# main.net
KiCad netlist of a schematic drawn in EAGLE
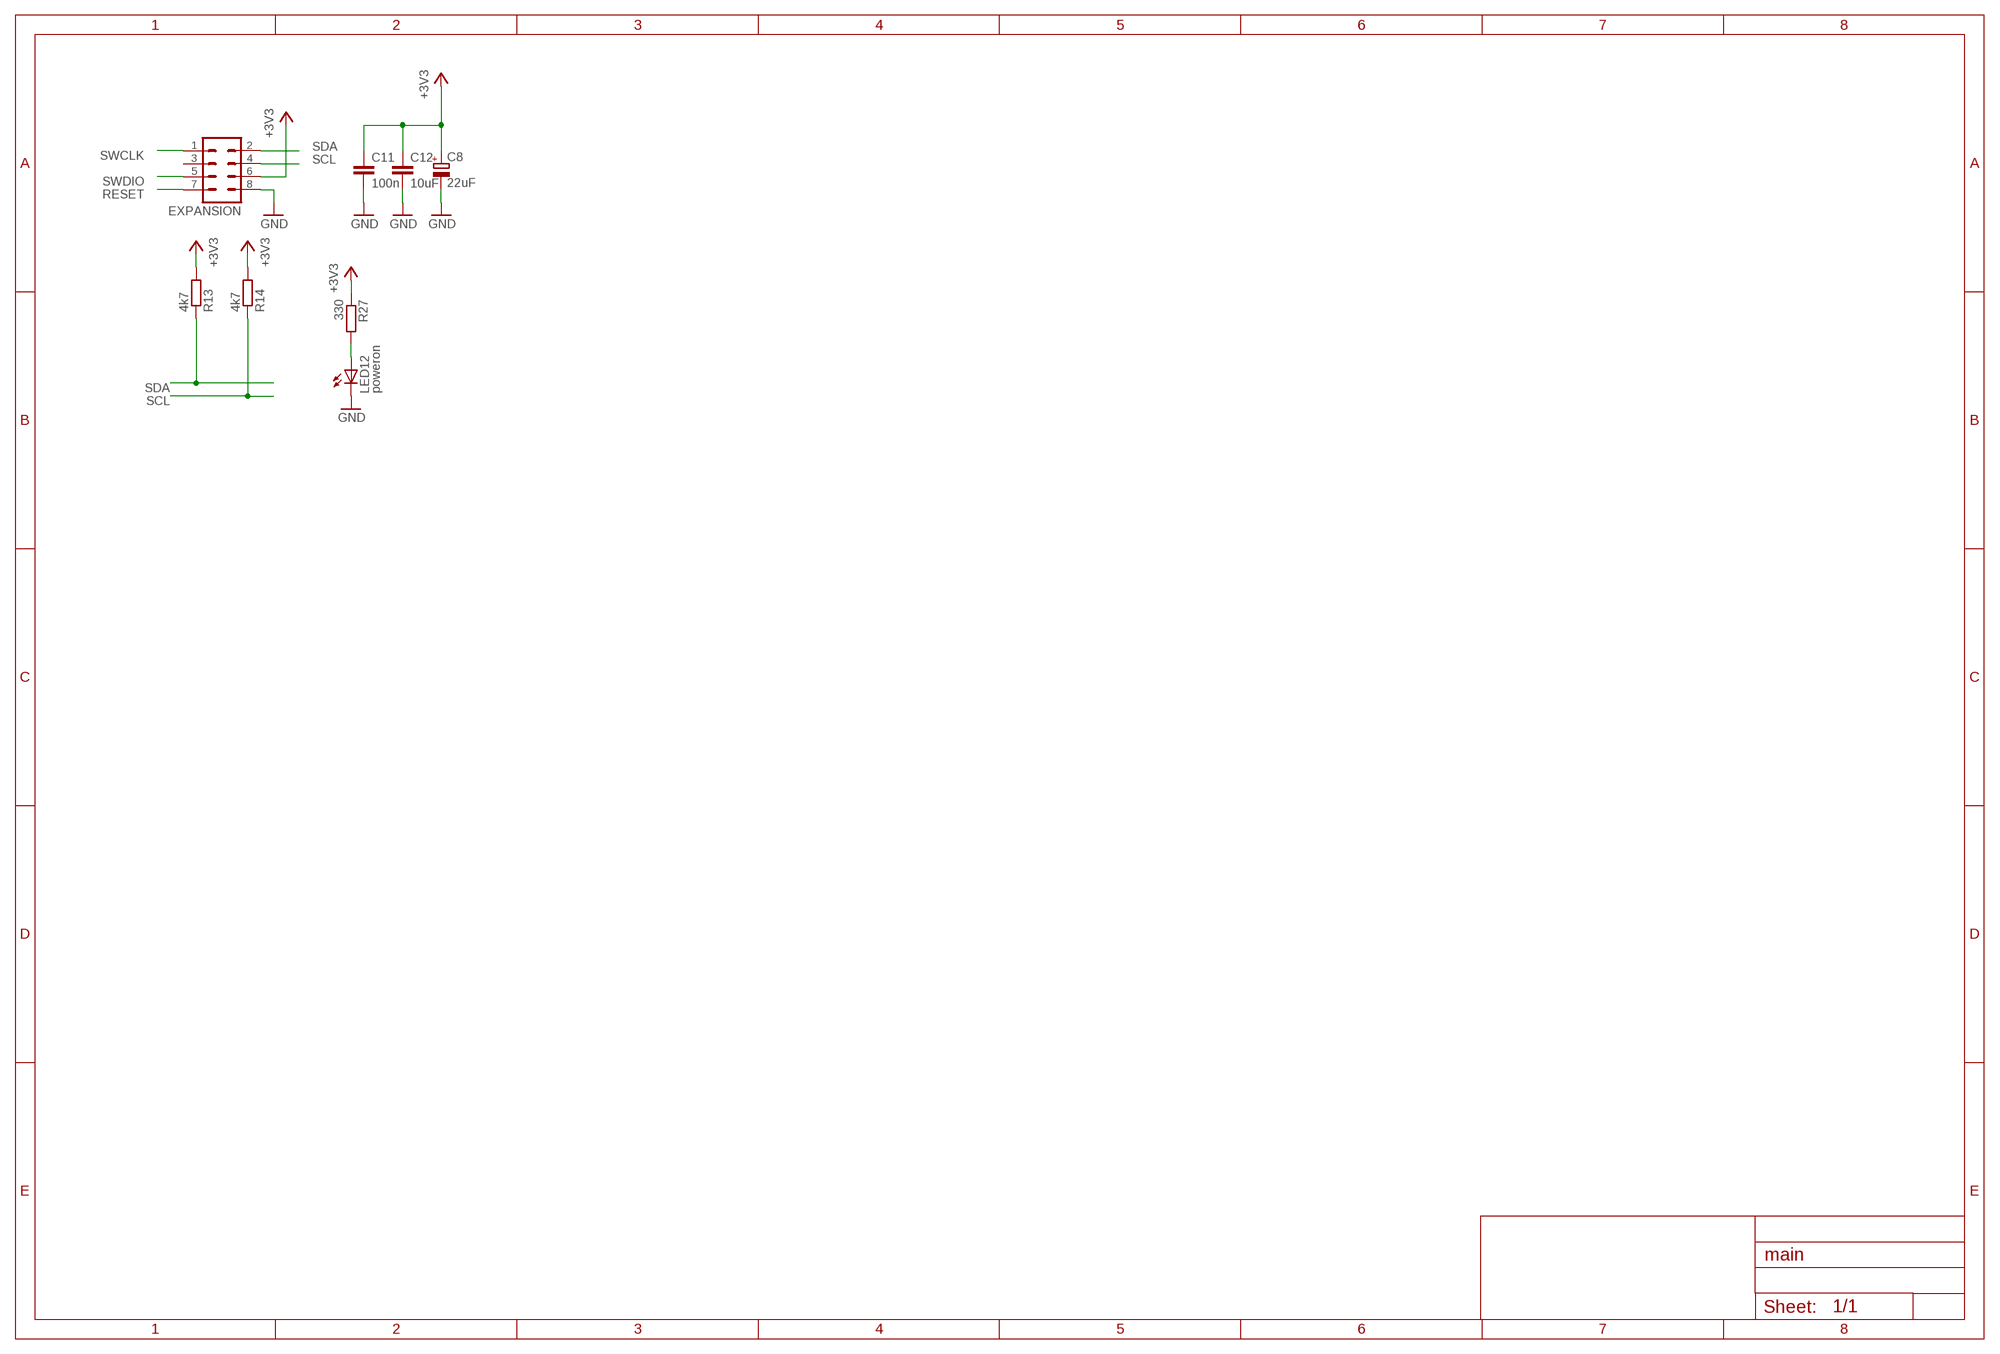
[diagram p0: schematic, sheet 1]

(export (version "E")
  (design (tool "Eeschema 10.0.6"))
  (components
    (comp (ref "C8")
      (value "22uF")
      (footprint "eagle-import:153CLV-0505")
      (libsource (lib "eagle-import") (part "CPOL-EU153CLV-0505"))
    )
    (comp (ref "C11")
      (value "100n")
      (footprint "eagle-import:C0805")
      (libsource (lib "eagle-import") (part "C-EUC0805"))
    )
    (comp (ref "C12")
      (value "10uF")
      (footprint "eagle-import:C0805")
      (libsource (lib "eagle-import") (part "C-EUC0805"))
    )
    (comp (ref "EXPANSION")
      (value "MA04-2")
      (footprint "eagle-import:MA04-2")
      (libsource (lib "eagle-import") (part "MA04-2"))
    )
    (comp (ref "LED12")
      (value "poweron")
      (footprint "eagle-import:CHIPLED_1206")
      (libsource (lib "eagle-import") (part "LEDCHIPLED_1206"))
    )
    (comp (ref "R13")
      (value "4k7")
      (footprint "eagle-import:M0805")
      (libsource (lib "eagle-import") (part "R-EU_M0805"))
    )
    (comp (ref "R14")
      (value "4k7")
      (footprint "eagle-import:M0805")
      (libsource (lib "eagle-import") (part "R-EU_M0805"))
    )
    (comp (ref "R27")
      (value "330")
      (footprint "eagle-import:M0805")
      (libsource (lib "eagle-import") (part "R-EU_M0805"))
    )
  )
  (nets
    (net (code "1") (name "+3V3") (class "Default")
      (node (ref "C11") (pin "1") (pinfunction "1_1") (pintype "passive"))
      (node (ref "C12") (pin "1") (pinfunction "1_1") (pintype "passive"))
      (node (ref "C8") (pin "+") (pinfunction "+_+") (pintype "passive"))
      (node (ref "EXPANSION") (pin "6") (pinfunction "6_6") (pintype "passive"))
      (node (ref "R13") (pin "2") (pinfunction "2_2") (pintype "passive"))
      (node (ref "R14") (pin "2") (pinfunction "2_2") (pintype "passive"))
      (node (ref "R27") (pin "1") (pinfunction "1_1") (pintype "passive"))
    )
    (net (code "2") (name "/RESET") (class "Default")
      (node (ref "EXPANSION") (pin "7") (pinfunction "7_7") (pintype "passive"))
    )
    (net (code "3") (name "/SCL") (class "Default")
      (node (ref "EXPANSION") (pin "4") (pinfunction "4_4") (pintype "passive"))
      (node (ref "R14") (pin "1") (pinfunction "1_1") (pintype "passive"))
    )
    (net (code "4") (name "/SDA") (class "Default")
      (node (ref "EXPANSION") (pin "2") (pinfunction "2_2") (pintype "passive"))
      (node (ref "R13") (pin "1") (pinfunction "1_1") (pintype "passive"))
    )
    (net (code "5") (name "/SWCLK") (class "Default")
      (node (ref "EXPANSION") (pin "1") (pinfunction "1_1") (pintype "passive"))
    )
    (net (code "6") (name "/SWDIO") (class "Default")
      (node (ref "EXPANSION") (pin "5") (pinfunction "5_5") (pintype "passive"))
    )
    (net (code "7") (name "GND") (class "Default")
      (node (ref "C11") (pin "2") (pinfunction "2_2") (pintype "passive"))
      (node (ref "C12") (pin "2") (pinfunction "2_2") (pintype "passive"))
      (node (ref "C8") (pin "-") (pinfunction "-_-") (pintype "passive"))
      (node (ref "EXPANSION") (pin "8") (pinfunction "8_8") (pintype "passive"))
      (node (ref "LED12") (pin "C") (pinfunction "C_C") (pintype "passive"))
    )
    (net (code "8") (name "Net-(LED12-PadA)") (class "Default")
      (node (ref "LED12") (pin "A") (pinfunction "A_A") (pintype "passive"))
      (node (ref "R27") (pin "2") (pinfunction "2_2") (pintype "passive"))
    )
    (net (code "9") (name "unconnected-(EXPANSION-Pad3)") (class "Default")
      (node (ref "EXPANSION") (pin "3") (pinfunction "3_3") (pintype "passive"))
    )
  )
)
